# MCU.net
KiCad netlist of a schematic drawn in Altium Designer
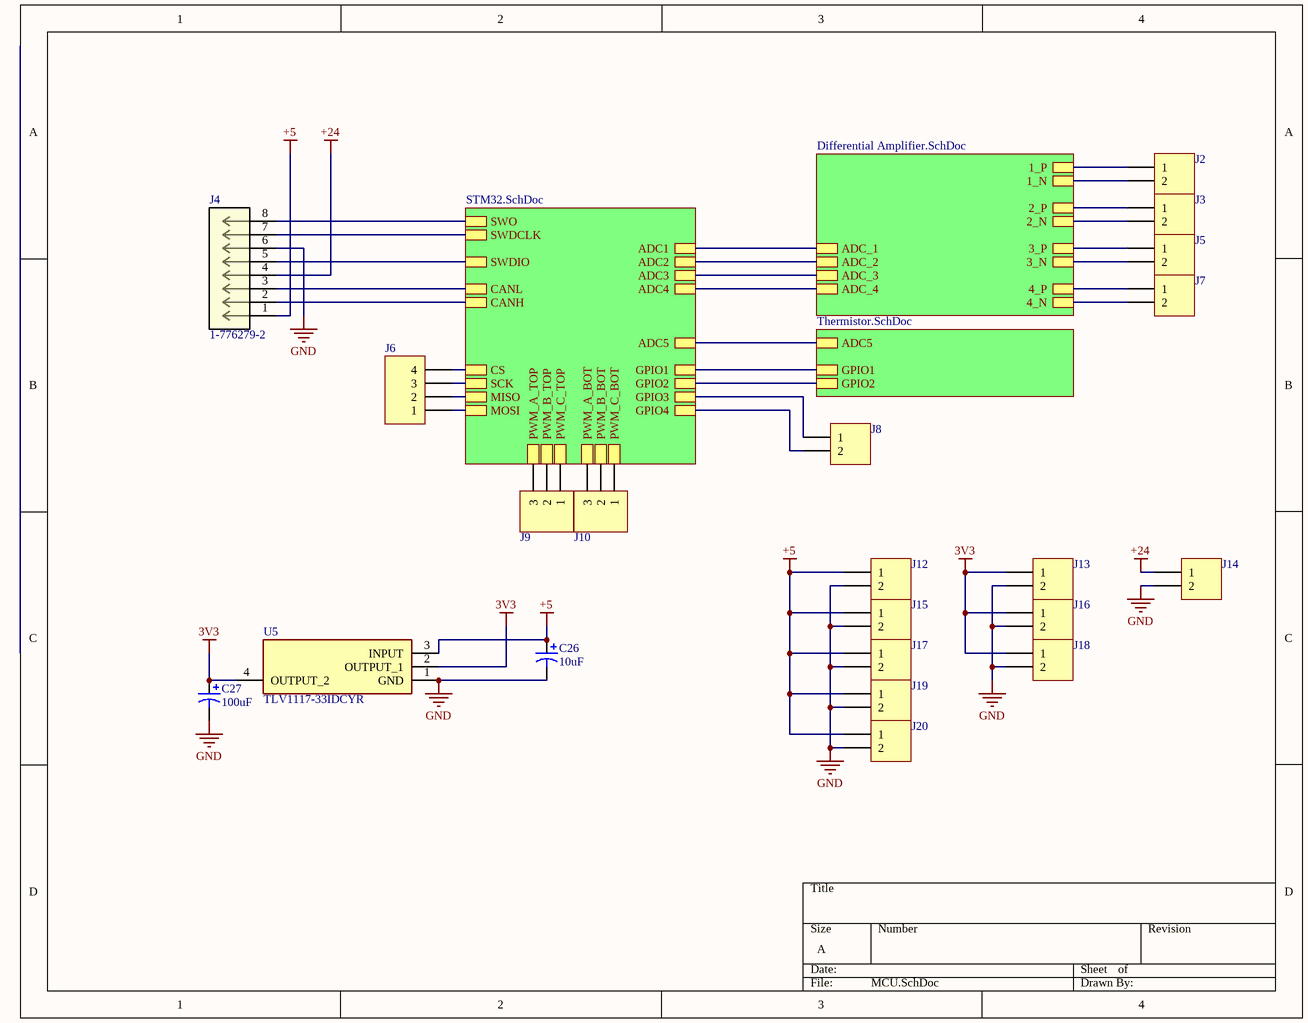
[diagram p0: MCU.SchDoc]

(export (version "E")
  (design (tool "Eeschema 10.0.6"))
  (components
    (comp (ref "C26")
      (value "10uF")
      (footprint "CAPAE660X800N")
      (description "Polarized Capacitor (Surface Mount)")
      (fields (field (name "Comment") "Cap Pol3") (field (name "PUBLISHER") "Altium Limited"))
      (libsource (lib "Miscellaneous Devices") (part "Cap Pol3"))
    )
    (comp (ref "C27")
      (value "100uF")
      (footprint "CAPAE660X800N")
      (description "Polarized Capacitor (Surface Mount)")
      (fields (field (name "Comment") "Cap Pol3") (field (name "PUBLISHER") "Altium Limited"))
      (libsource (lib "Miscellaneous Devices") (part "Cap Pol3"))
    )
    (comp (ref "J2")
      (value "Header 2")
      (footprint "HDR1X2")
      (description "Header, 2-Pin")
      (fields (field (name "PUBLISHER") "Altium Limited"))
      (libsource (lib "Miscellaneous Connectors") (part "Header 2"))
    )
    (comp (ref "J3")
      (value "Header 2")
      (footprint "HDR1X2")
      (description "Header, 2-Pin")
      (fields (field (name "PUBLISHER") "Altium Limited"))
      (libsource (lib "Miscellaneous Connectors") (part "Header 2"))
    )
    (comp (ref "J4")
      (value "1-776279-2")
      (footprint "CONN8_776279_TEC")
      (description "8 POS RIGHT ANGLE HEADER ASSY")
      (fields (field (name "COPYRIGHT") "Copyright (C) 2016 Accelerated Designs. All rights reserved"))
      (libsource (lib "Motor Controller") (part "1-776279-2"))
    )
    (comp (ref "J5")
      (value "Header 2")
      (footprint "HDR1X2")
      (description "Header, 2-Pin")
      (fields (field (name "PUBLISHER") "Altium Limited"))
      (libsource (lib "Miscellaneous Connectors") (part "Header 2"))
    )
    (comp (ref "J6")
      (value "Header 4")
      (footprint "HDR1X4")
      (description "Header, 4-Pin")
      (fields (field (name "PUBLISHER") "Altium Limited"))
      (libsource (lib "Miscellaneous Connectors") (part "Header 4"))
    )
    (comp (ref "J7")
      (value "Header 2")
      (footprint "HDR1X2")
      (description "Header, 2-Pin")
      (fields (field (name "PUBLISHER") "Altium Limited"))
      (libsource (lib "Miscellaneous Connectors") (part "Header 2"))
    )
    (comp (ref "J8")
      (value "Header 2")
      (footprint "HDR1X2")
      (description "Header, 2-Pin")
      (fields (field (name "PUBLISHER") "Altium Limited"))
      (libsource (lib "Miscellaneous Connectors") (part "Header 2"))
    )
    (comp (ref "J9")
      (value "Header 3")
      (footprint "HDR1X3")
      (description "Header, 3-Pin")
      (fields (field (name "PUBLISHER") "Altium Limited"))
      (libsource (lib "Miscellaneous Connectors") (part "Header 3"))
    )
    (comp (ref "J10")
      (value "Header 3")
      (footprint "HDR1X3")
      (description "Header, 3-Pin")
      (fields (field (name "PUBLISHER") "Altium Limited"))
      (libsource (lib "Miscellaneous Connectors") (part "Header 3"))
    )
    (comp (ref "J12")
      (value "Header 2")
      (footprint "HDR1X2")
      (description "Header, 2-Pin")
      (fields (field (name "PUBLISHER") "Altium Limited"))
      (libsource (lib "Miscellaneous Connectors") (part "Header 2"))
    )
    (comp (ref "J13")
      (value "Header 2")
      (footprint "HDR1X2")
      (description "Header, 2-Pin")
      (fields (field (name "PUBLISHER") "Altium Limited"))
      (libsource (lib "Miscellaneous Connectors") (part "Header 2"))
    )
    (comp (ref "J14")
      (value "Header 2")
      (footprint "HDR1X2")
      (description "Header, 2-Pin")
      (fields (field (name "PUBLISHER") "Altium Limited"))
      (libsource (lib "Miscellaneous Connectors") (part "Header 2"))
    )
    (comp (ref "J15")
      (value "Header 2")
      (footprint "HDR1X2")
      (description "Header, 2-Pin")
      (fields (field (name "PUBLISHER") "Altium Limited"))
      (libsource (lib "Miscellaneous Connectors") (part "Header 2"))
    )
    (comp (ref "J16")
      (value "Header 2")
      (footprint "HDR1X2")
      (description "Header, 2-Pin")
      (fields (field (name "PUBLISHER") "Altium Limited"))
      (libsource (lib "Miscellaneous Connectors") (part "Header 2"))
    )
    (comp (ref "J17")
      (value "Header 2")
      (footprint "HDR1X2")
      (description "Header, 2-Pin")
      (fields (field (name "PUBLISHER") "Altium Limited"))
      (libsource (lib "Miscellaneous Connectors") (part "Header 2"))
    )
    (comp (ref "J18")
      (value "Header 2")
      (footprint "HDR1X2")
      (description "Header, 2-Pin")
      (fields (field (name "PUBLISHER") "Altium Limited"))
      (libsource (lib "Miscellaneous Connectors") (part "Header 2"))
    )
    (comp (ref "J19")
      (value "Header 2")
      (footprint "HDR1X2")
      (description "Header, 2-Pin")
      (fields (field (name "PUBLISHER") "Altium Limited"))
      (libsource (lib "Miscellaneous Connectors") (part "Header 2"))
    )
    (comp (ref "J20")
      (value "Header 2")
      (footprint "HDR1X2")
      (description "Header, 2-Pin")
      (fields (field (name "PUBLISHER") "Altium Limited"))
      (libsource (lib "Miscellaneous Connectors") (part "Header 2"))
    )
    (comp (ref "U5")
      (value "TLV1117-33IDCYR")
      (footprint "Motor Controller:SOT230P700X180-4N")
      (description "Integrated Circuit")
      (fields (field (name "MOUSER PART NUMBER") "595-TLV1117-33IDCYR"))
      (libsource (lib "Motor Controller") (part "TLV1117-33IDCYR"))
    )
  )
  (nets
    (net (code "1") (name "+5") (class "Default")
      (node (ref "C26") (pin "1") (pinfunction "1_1") (pintype "passive"))
      (node (ref "J12") (pin "1") (pinfunction "1_1") (pintype "passive"))
      (node (ref "J15") (pin "1") (pinfunction "1_1") (pintype "passive"))
      (node (ref "J17") (pin "1") (pinfunction "1_1") (pintype "passive"))
      (node (ref "J19") (pin "1") (pinfunction "1_1") (pintype "passive"))
      (node (ref "J20") (pin "1") (pinfunction "1_1") (pintype "passive"))
      (node (ref "J4") (pin "1") (pinfunction "1_1") (pintype "passive"))
      (node (ref "U5") (pin "3") (pinfunction "INPUT_3") (pintype "passive"))
    )
    (net (code "2") (name "+24") (class "Default")
      (node (ref "J14") (pin "1") (pinfunction "1_1") (pintype "passive"))
      (node (ref "J4") (pin "4") (pinfunction "4_4") (pintype "passive"))
    )
    (net (code "3") (name "/1_N") (class "Default")
      (node (ref "J2") (pin "2") (pinfunction "2_2") (pintype "passive"))
    )
    (net (code "4") (name "/1_P") (class "Default")
      (node (ref "J2") (pin "1") (pinfunction "1_1") (pintype "passive"))
    )
    (net (code "5") (name "/2_N") (class "Default")
      (node (ref "J3") (pin "2") (pinfunction "2_2") (pintype "passive"))
    )
    (net (code "6") (name "/2_P") (class "Default")
      (node (ref "J3") (pin "1") (pinfunction "1_1") (pintype "passive"))
    )
    (net (code "7") (name "/3_N") (class "Default")
      (node (ref "J5") (pin "2") (pinfunction "2_2") (pintype "passive"))
    )
    (net (code "8") (name "/3_P") (class "Default")
      (node (ref "J5") (pin "1") (pinfunction "1_1") (pintype "passive"))
    )
    (net (code "9") (name "/4_N") (class "Default")
      (node (ref "J7") (pin "2") (pinfunction "2_2") (pintype "passive"))
    )
    (net (code "10") (name "/4_P") (class "Default")
      (node (ref "J7") (pin "1") (pinfunction "1_1") (pintype "passive"))
    )
    (net (code "16") (name "/CANH") (class "Default")
      (node (ref "J4") (pin "2") (pinfunction "2_2") (pintype "passive"))
    )
    (net (code "17") (name "/CANL") (class "Default")
      (node (ref "J4") (pin "3") (pinfunction "3_3") (pintype "passive"))
    )
    (net (code "18") (name "/CS") (class "Default")
      (node (ref "J6") (pin "4") (pinfunction "4_4") (pintype "passive"))
    )
    (net (code "21") (name "/GPIO3") (class "Default")
      (node (ref "J8") (pin "1") (pinfunction "1_1") (pintype "passive"))
    )
    (net (code "22") (name "/GPIO4") (class "Default")
      (node (ref "J8") (pin "2") (pinfunction "2_2") (pintype "passive"))
    )
    (net (code "23") (name "/MISO") (class "Default")
      (node (ref "J6") (pin "2") (pinfunction "2_2") (pintype "passive"))
    )
    (net (code "24") (name "/MOSI") (class "Default")
      (node (ref "J6") (pin "1") (pinfunction "1_1") (pintype "passive"))
    )
    (net (code "25") (name "/PWM_A_BOT") (class "Default")
      (node (ref "J10") (pin "3") (pinfunction "3_3") (pintype "passive"))
    )
    (net (code "26") (name "/PWM_A_TOP") (class "Default")
      (node (ref "J9") (pin "3") (pinfunction "3_3") (pintype "passive"))
    )
    (net (code "27") (name "/PWM_B_BOT") (class "Default")
      (node (ref "J10") (pin "2") (pinfunction "2_2") (pintype "passive"))
    )
    (net (code "28") (name "/PWM_B_TOP") (class "Default")
      (node (ref "J9") (pin "2") (pinfunction "2_2") (pintype "passive"))
    )
    (net (code "29") (name "/PWM_C_BOT") (class "Default")
      (node (ref "J10") (pin "1") (pinfunction "1_1") (pintype "passive"))
    )
    (net (code "30") (name "/PWM_C_TOP") (class "Default")
      (node (ref "J9") (pin "1") (pinfunction "1_1") (pintype "passive"))
    )
    (net (code "31") (name "/SCK") (class "Default")
      (node (ref "J6") (pin "3") (pinfunction "3_3") (pintype "passive"))
    )
    (net (code "32") (name "/SWDCLK") (class "Default")
      (node (ref "J4") (pin "7") (pinfunction "7_7") (pintype "passive"))
    )
    (net (code "33") (name "/SWDIO") (class "Default")
      (node (ref "J4") (pin "5") (pinfunction "5_5") (pintype "passive"))
    )
    (net (code "34") (name "/SWO") (class "Default")
      (node (ref "J4") (pin "8") (pinfunction "8_8") (pintype "passive"))
    )
    (net (code "35") (name "3V3") (class "Default")
      (node (ref "C27") (pin "1") (pinfunction "1_1") (pintype "passive"))
      (node (ref "J13") (pin "1") (pinfunction "1_1") (pintype "passive"))
      (node (ref "J16") (pin "1") (pinfunction "1_1") (pintype "passive"))
      (node (ref "J18") (pin "1") (pinfunction "1_1") (pintype "passive"))
      (node (ref "U5") (pin "2") (pinfunction "OUTPUT_1_2") (pintype "passive"))
      (node (ref "U5") (pin "4") (pinfunction "OUTPUT_2_4") (pintype "passive"))
    )
    (net (code "36") (name "GND") (class "Default")
      (node (ref "C26") (pin "2") (pinfunction "2_2") (pintype "passive"))
      (node (ref "C27") (pin "2") (pinfunction "2_2") (pintype "passive"))
      (node (ref "J12") (pin "2") (pinfunction "2_2") (pintype "passive"))
      (node (ref "J13") (pin "2") (pinfunction "2_2") (pintype "passive"))
      (node (ref "J14") (pin "2") (pinfunction "2_2") (pintype "passive"))
      (node (ref "J15") (pin "2") (pinfunction "2_2") (pintype "passive"))
      (node (ref "J16") (pin "2") (pinfunction "2_2") (pintype "passive"))
      (node (ref "J17") (pin "2") (pinfunction "2_2") (pintype "passive"))
      (node (ref "J18") (pin "2") (pinfunction "2_2") (pintype "passive"))
      (node (ref "J19") (pin "2") (pinfunction "2_2") (pintype "passive"))
      (node (ref "J20") (pin "2") (pinfunction "2_2") (pintype "passive"))
      (node (ref "J4") (pin "6") (pinfunction "6_6") (pintype "passive"))
      (node (ref "U5") (pin "1") (pinfunction "GND_1") (pintype "passive"))
    )
  )
)
